# Sheet1.net
KiCad netlist of a schematic drawn in Altium Designer
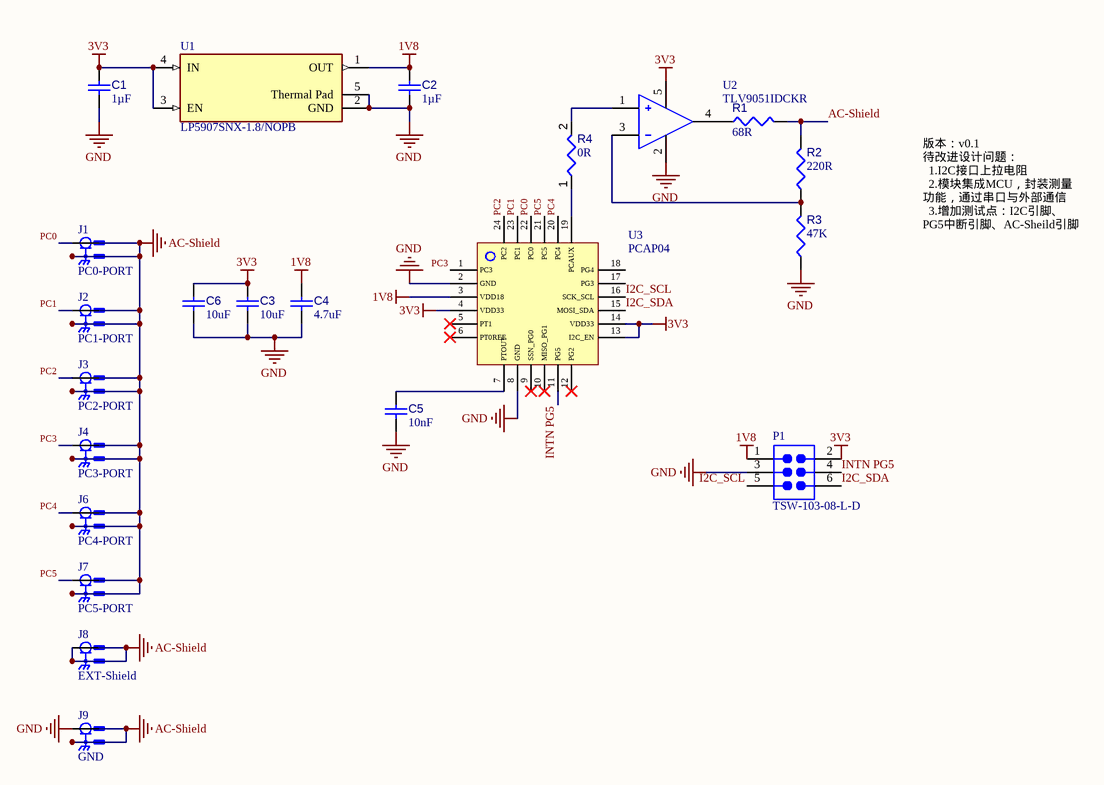
[diagram p0: Sheet1.SchDoc]

(export (version "E")
  (design (tool "Eeschema 10.0.6"))
  (components
    (comp (ref "C1")
      (value "1µF")
      (footprint "CAPC0402(1005)60_L")
      (description "Chip Capacitor, 1µF +/-20%, 10V, 0402, Thickness 0.6 mm")
      (fields (field (name "TOLERANCE") "10%") (field (name "Comment") "Capacitor 1µF +/-20% 10V 0402"))
      (libsource (lib "DigiPCBA Workspace") (part "CAP-NP-2"))
    )
    (comp (ref "C2")
      (value "1µF")
      (footprint "CAPC0402(1005)60_L")
      (description "Chip Capacitor, 1µF +/-20%, 10V, 0402, Thickness 0.6 mm")
      (fields (field (name "TOLERANCE") "10%") (field (name "Comment") "Capacitor 1µF +/-20% 10V 0402"))
      (libsource (lib "DigiPCBA Workspace") (part "CAP-NP-2"))
    )
    (comp (ref "C3")
      (value "10uF")
      (footprint "CAPC0402(1005)60_L")
      (description "Chip Capacitor, 10µF +/-40%, 6.3V, 0402, Thickness 0.6 mm")
      (fields (field (name "TOLERANCE") "10%") (field (name "Comment") "Capacitor 10µF +/-40% 6.3V 0402"))
      (libsource (lib "DigiPCBA Workspace") (part "CAP-NP-2"))
    )
    (comp (ref "C4")
      (value "4.7uF")
      (footprint "CAPC0402(1005)60_L")
      (description "Chip Capacitor, 10µF +/-40%, 6.3V, 0402, Thickness 0.6 mm")
      (fields (field (name "TOLERANCE") "10%") (field (name "Comment") "Capacitor 10µF +/-40% 6.3V 0402"))
      (libsource (lib "DigiPCBA Workspace") (part "CAP-NP-2"))
    )
    (comp (ref "C5")
      (value "10nF")
      (footprint "CAPC0402(1005)60_L")
      (description "Chip Capacitor, 10nF +/-20%, 50V, 0402, Thickness 0.6 mm")
      (fields (field (name "TOLERANCE") "5%") (field (name "Comment") "Capacitor 10nF +/-20% 50V 0402"))
      (libsource (lib "DigiPCBA Workspace") (part "CAP-NP-2"))
    )
    (comp (ref "C6")
      (value "10uF")
      (footprint "CAPC0402(1005)60_L")
      (description "Chip Capacitor, 10µF +/-40%, 6.3V, 0402, Thickness 0.6 mm")
      (fields (field (name "TOLERANCE") "10%") (field (name "Comment") "Capacitor 10µF +/-40% 6.3V 0402"))
      (libsource (lib "DigiPCBA Workspace") (part "CAP-NP-2"))
    )
    (comp (ref "J1")
      (value "PC0-PORT")
      (footprint "LINX_CONMHF4-SMD-G-T")
      (description "IPEX MHF4 Connector Jack, Male Pin 50Ohm Surface Mount Solder")
      (fields (field (name "MP") "CONMHF4-SMD-G-T") (field (name "MF") "Linx Technologies Inc."))
      (libsource (lib "DigiPCBA Workspace") (part "CONMHF4-SMD-G-T"))
    )
    (comp (ref "J2")
      (value "PC1-PORT")
      (footprint "LINX_CONMHF4-SMD-G-T")
      (description "IPEX MHF4 Connector Jack, Male Pin 50Ohm Surface Mount Solder")
      (fields (field (name "MP") "CONMHF4-SMD-G-T") (field (name "MF") "Linx Technologies Inc."))
      (libsource (lib "DigiPCBA Workspace") (part "CONMHF4-SMD-G-T"))
    )
    (comp (ref "J3")
      (value "PC2-PORT")
      (footprint "LINX_CONMHF4-SMD-G-T")
      (description "IPEX MHF4 Connector Jack, Male Pin 50Ohm Surface Mount Solder")
      (fields (field (name "MP") "CONMHF4-SMD-G-T") (field (name "MF") "Linx Technologies Inc."))
      (libsource (lib "DigiPCBA Workspace") (part "CONMHF4-SMD-G-T"))
    )
    (comp (ref "J4")
      (value "PC3-PORT")
      (footprint "LINX_CONMHF4-SMD-G-T")
      (description "IPEX MHF4 Connector Jack, Male Pin 50Ohm Surface Mount Solder")
      (fields (field (name "MP") "CONMHF4-SMD-G-T") (field (name "MF") "Linx Technologies Inc."))
      (libsource (lib "DigiPCBA Workspace") (part "CONMHF4-SMD-G-T"))
    )
    (comp (ref "J6")
      (value "PC4-PORT")
      (footprint "LINX_CONMHF4-SMD-G-T")
      (description "IPEX MHF4 Connector Jack, Male Pin 50Ohm Surface Mount Solder")
      (fields (field (name "MP") "CONMHF4-SMD-G-T") (field (name "MF") "Linx Technologies Inc."))
      (libsource (lib "DigiPCBA Workspace") (part "CONMHF4-SMD-G-T"))
    )
    (comp (ref "J7")
      (value "PC5-PORT")
      (footprint "LINX_CONMHF4-SMD-G-T")
      (description "IPEX MHF4 Connector Jack, Male Pin 50Ohm Surface Mount Solder")
      (fields (field (name "MP") "CONMHF4-SMD-G-T") (field (name "MF") "Linx Technologies Inc."))
      (libsource (lib "DigiPCBA Workspace") (part "CONMHF4-SMD-G-T"))
    )
    (comp (ref "J8")
      (value "EXT-Shield")
      (footprint "LINX_CONMHF4-SMD-G-T")
      (description "IPEX MHF4 Connector Jack, Male Pin 50Ohm Surface Mount Solder")
      (fields (field (name "MP") "CONMHF4-SMD-G-T") (field (name "MF") "Linx Technologies Inc."))
      (libsource (lib "DigiPCBA Workspace") (part "CONMHF4-SMD-G-T"))
    )
    (comp (ref "J9")
      (value "GND")
      (footprint "LINX_CONMHF4-SMD-G-T")
      (description "IPEX MHF4 Connector Jack, Male Pin 50Ohm Surface Mount Solder")
      (fields (field (name "MP") "CONMHF4-SMD-G-T") (field (name "MF") "Linx Technologies Inc."))
      (libsource (lib "DigiPCBA Workspace") (part "CONMHF4-SMD-G-T"))
    )
    (comp (ref "P1")
      (value "TSW-103-08-L-D")
      (footprint "SMTC-TSW-103-08-X-D")
      (description "0.025\" SQ Post Header, Through-hole, Vertical, -55 to 125 degC, 2.54 mm Pitch, 6-Pin, Male, RoHS")
      (fields (field (name "MANUFACTURER") "Samtec"))
      (libsource (lib "Altium Content Vault") (part "SMTC-TSW-103-08-X-D"))
    )
    (comp (ref "R1")
      (value "68R")
      (footprint "RESC0402(1005)_L")
      (description "Chip Resistor, 10 Ohms, +/-1 %, 63 mW, -55 to 155 degC, 0402")
      (fields (field (name "TOLERANCE") "1%") (field (name "POWER") "63mW"))
      (libsource (lib "DigiPCBA Workspace") (part "RES-2"))
    )
    (comp (ref "R2")
      (value "220R")
      (footprint "RESC0402(1005)_L")
      (description "Chip Resistor, 10 Ohms, +/-1 %, 63 mW, -55 to 155 degC, 0402")
      (fields (field (name "TOLERANCE") "1%") (field (name "POWER") "63mW"))
      (libsource (lib "DigiPCBA Workspace") (part "RES-2"))
    )
    (comp (ref "R3")
      (value "47K")
      (footprint "RESC0402(1005)_L")
      (description "Chip Resistor, 10 Ohms, +/-1 %, 63 mW, -55 to 155 degC, 0402")
      (fields (field (name "TOLERANCE") "1%") (field (name "POWER") "63mW"))
      (libsource (lib "DigiPCBA Workspace") (part "RES-2"))
    )
    (comp (ref "R4")
      (value "0R")
      (footprint "RESC0402(1005)_L")
      (description "Chip Resistor, 10 Ohms, +/-1 %, 63 mW, -55 to 155 degC, 0402")
      (fields (field (name "TOLERANCE") "1%") (field (name "POWER") "63mW"))
      (libsource (lib "") (part "RES-2_1"))
    )
    (comp (ref "U1")
      (value "LP5907SNX-1.8/NOPB")
      (footprint "FP-DQN0004A-MFG")
      (description "None")
      (libsource (lib "Altium Content Vault") (part "d9ea95ee919af165dc366e5aa64fdc0"))
    )
    (comp (ref "U2")
      (value "TLV9051IDCKR")
      (footprint "FP-DCK0005A-IPC_A")
      (description "IC OPAMP GP 1 CIRCUIT SC70-5")
      (libsource (lib "Altium Content Vault") (part "d26da39eff9d56ed2cb7351b5ff93ab"))
    )
    (comp (ref "U3")
      (value "PCAP04")
      (footprint "QFN-24-PAD")
      (description "CDC IC")
      (libsource (lib "Schlib1") (part "PCAP04"))
    )
  )
  (nets
    (net (code "1") (name "/I2C_SCL") (class "Default")
      (node (ref "P1") (pin "5") (pinfunction "5_5") (pintype "passive"))
      (node (ref "U3") (pin "16") (pinfunction "SCK_SCL_16") (pintype "passive"))
    )
    (net (code "2") (name "/I2C_SDA") (class "Default")
      (node (ref "P1") (pin "6") (pinfunction "6_6") (pintype "passive"))
      (node (ref "U3") (pin "15") (pinfunction "MOSI_SDA_15") (pintype "passive"))
    )
    (net (code "3") (name "/INTN PG5") (class "Default")
      (node (ref "P1") (pin "4") (pinfunction "4_4") (pintype "passive"))
      (node (ref "U3") (pin "11") (pinfunction "PG5_11") (pintype "passive"))
    )
    (net (code "4") (name "/PC0") (class "Default")
      (node (ref "J1") (pin "1") (pinfunction "1_1") (pintype "passive"))
      (node (ref "U3") (pin "22") (pinfunction "PC0_22") (pintype "passive"))
    )
    (net (code "5") (name "/PC1") (class "Default")
      (node (ref "J2") (pin "1") (pinfunction "1_1") (pintype "passive"))
      (node (ref "U3") (pin "23") (pinfunction "PC1_23") (pintype "passive"))
    )
    (net (code "6") (name "/PC2") (class "Default")
      (node (ref "J3") (pin "1") (pinfunction "1_1") (pintype "passive"))
      (node (ref "U3") (pin "24") (pinfunction "PC2_24") (pintype "passive"))
    )
    (net (code "7") (name "/PC3") (class "Default")
      (node (ref "J4") (pin "1") (pinfunction "1_1") (pintype "passive"))
      (node (ref "U3") (pin "1") (pinfunction "PC3_1") (pintype "passive"))
    )
    (net (code "8") (name "/PC4") (class "Default")
      (node (ref "J6") (pin "1") (pinfunction "1_1") (pintype "passive"))
      (node (ref "U3") (pin "20") (pinfunction "PC4_20") (pintype "passive"))
    )
    (net (code "9") (name "/PC5") (class "Default")
      (node (ref "J7") (pin "1") (pinfunction "1_1") (pintype "passive"))
      (node (ref "U3") (pin "21") (pinfunction "PC5_21") (pintype "passive"))
    )
    (net (code "10") (name "1V8") (class "Default")
      (node (ref "C2") (pin "1") (pinfunction "1_1") (pintype "passive"))
      (node (ref "C4") (pin "2") (pinfunction "2_2") (pintype "passive"))
      (node (ref "P1") (pin "1") (pinfunction "1_1") (pintype "passive"))
      (node (ref "U1") (pin "1") (pinfunction "OUT_1") (pintype "output"))
      (node (ref "U3") (pin "3") (pinfunction "VDD18_3") (pintype "passive"))
    )
    (net (code "11") (name "3V3") (class "Default")
      (node (ref "C1") (pin "1") (pinfunction "1_1") (pintype "passive"))
      (node (ref "C3") (pin "2") (pinfunction "2_2") (pintype "passive"))
      (node (ref "C6") (pin "2") (pinfunction "2_2") (pintype "passive"))
      (node (ref "P1") (pin "2") (pinfunction "2_2") (pintype "passive"))
      (node (ref "U1") (pin "3") (pinfunction "EN_3") (pintype "input"))
      (node (ref "U1") (pin "4") (pinfunction "IN_4") (pintype "input"))
      (node (ref "U2") (pin "5") (pinfunction "V+_5") (pintype "power_in"))
      (node (ref "U3") (pin "13") (pinfunction "I2C_EN_13") (pintype "passive"))
      (node (ref "U3") (pin "14") (pinfunction "VDD33_14") (pintype "passive"))
      (node (ref "U3") (pin "4") (pinfunction "VDD33_4") (pintype "passive"))
    )
    (net (code "12") (name "AC-Shield") (class "Default")
      (node (ref "J1") (pin "S1") (pinfunction "2_S1") (pintype "passive"))
      (node (ref "J1") (pin "S2") (pinfunction "2_S2") (pintype "passive"))
      (node (ref "J1") (pin "S3") (pinfunction "2_S3") (pintype "passive"))
      (node (ref "J2") (pin "S1") (pinfunction "2_S1") (pintype "passive"))
      (node (ref "J2") (pin "S2") (pinfunction "2_S2") (pintype "passive"))
      (node (ref "J2") (pin "S3") (pinfunction "2_S3") (pintype "passive"))
      (node (ref "J3") (pin "S1") (pinfunction "2_S1") (pintype "passive"))
      (node (ref "J3") (pin "S2") (pinfunction "2_S2") (pintype "passive"))
      (node (ref "J3") (pin "S3") (pinfunction "2_S3") (pintype "passive"))
      (node (ref "J4") (pin "S1") (pinfunction "2_S1") (pintype "passive"))
      (node (ref "J4") (pin "S2") (pinfunction "2_S2") (pintype "passive"))
      (node (ref "J4") (pin "S3") (pinfunction "2_S3") (pintype "passive"))
      (node (ref "J6") (pin "S1") (pinfunction "2_S1") (pintype "passive"))
      (node (ref "J6") (pin "S2") (pinfunction "2_S2") (pintype "passive"))
      (node (ref "J6") (pin "S3") (pinfunction "2_S3") (pintype "passive"))
      (node (ref "J7") (pin "S1") (pinfunction "2_S1") (pintype "passive"))
      (node (ref "J7") (pin "S2") (pinfunction "2_S2") (pintype "passive"))
      (node (ref "J7") (pin "S3") (pinfunction "2_S3") (pintype "passive"))
      (node (ref "J8") (pin "1") (pinfunction "1_1") (pintype "passive"))
      (node (ref "J8") (pin "S1") (pinfunction "2_S1") (pintype "passive"))
      (node (ref "J8") (pin "S2") (pinfunction "2_S2") (pintype "passive"))
      (node (ref "J8") (pin "S3") (pinfunction "2_S3") (pintype "passive"))
      (node (ref "J9") (pin "S1") (pinfunction "2_S1") (pintype "passive"))
      (node (ref "J9") (pin "S2") (pinfunction "2_S2") (pintype "passive"))
      (node (ref "J9") (pin "S3") (pinfunction "2_S3") (pintype "passive"))
      (node (ref "R1") (pin "2") (pinfunction "2_2") (pintype "passive"))
      (node (ref "R2") (pin "2") (pinfunction "2_2") (pintype "passive"))
    )
    (net (code "13") (name "GND") (class "Default")
      (node (ref "C1") (pin "2") (pinfunction "2_2") (pintype "passive"))
      (node (ref "C2") (pin "2") (pinfunction "2_2") (pintype "passive"))
      (node (ref "C3") (pin "1") (pinfunction "1_1") (pintype "passive"))
      (node (ref "C4") (pin "1") (pinfunction "1_1") (pintype "passive"))
      (node (ref "C5") (pin "1") (pinfunction "1_1") (pintype "passive"))
      (node (ref "C6") (pin "1") (pinfunction "1_1") (pintype "passive"))
      (node (ref "J9") (pin "1") (pinfunction "1_1") (pintype "passive"))
      (node (ref "P1") (pin "3") (pinfunction "3_3") (pintype "passive"))
      (node (ref "R3") (pin "1") (pinfunction "1_1") (pintype "passive"))
      (node (ref "U1") (pin "2") (pinfunction "GND_2") (pintype "power_in"))
      (node (ref "U1") (pin "5") (pinfunction "Thermal_Pad_5") (pintype "power_in"))
      (node (ref "U2") (pin "2") (pinfunction "V-_2") (pintype "power_in"))
      (node (ref "U3") (pin "2") (pinfunction "GND_2") (pintype "passive"))
      (node (ref "U3") (pin "8") (pinfunction "GND_8") (pintype "passive"))
    )
    (net (code "14") (name "Net-(U2-IN+)") (class "Default")
      (node (ref "R4") (pin "2") (pinfunction "2_2") (pintype "passive"))
      (node (ref "U2") (pin "1") (pinfunction "IN+_1") (pintype "tri_state"))
    )
    (net (code "15") (name "Net-(U2-IN-)") (class "Default")
      (node (ref "R2") (pin "1") (pinfunction "1_1") (pintype "passive"))
      (node (ref "R3") (pin "2") (pinfunction "2_2") (pintype "passive"))
      (node (ref "U2") (pin "3") (pinfunction "IN-_3") (pintype "tri_state"))
    )
    (net (code "16") (name "Net-(U2-OUT)") (class "Default")
      (node (ref "R1") (pin "1") (pinfunction "1_1") (pintype "passive"))
      (node (ref "U2") (pin "4") (pinfunction "OUT_4") (pintype "passive"))
    )
    (net (code "17") (name "Net-(U3-PCAUX)") (class "Default")
      (node (ref "R4") (pin "1") (pinfunction "1_1") (pintype "passive"))
      (node (ref "U3") (pin "19") (pinfunction "PCAUX_19") (pintype "passive"))
    )
    (net (code "18") (name "Net-(U3-PTOUT)") (class "Default")
      (node (ref "C5") (pin "2") (pinfunction "2_2") (pintype "passive"))
      (node (ref "U3") (pin "7") (pinfunction "PTOUT_7") (pintype "passive"))
    )
    (net (code "19") (name "unconnected-(U3-MISO_PG1-Pad10)") (class "Default")
      (node (ref "U3") (pin "10") (pinfunction "MISO_PG1_10") (pintype "passive+no_connect"))
    )
    (net (code "20") (name "unconnected-(U3-PG2-Pad12)") (class "Default")
      (node (ref "U3") (pin "12") (pinfunction "PG2_12") (pintype "passive+no_connect"))
    )
    (net (code "21") (name "unconnected-(U3-PG3-Pad17)") (class "Default")
      (node (ref "U3") (pin "17") (pinfunction "PG3_17") (pintype "passive"))
    )
    (net (code "22") (name "unconnected-(U3-PG4-Pad18)") (class "Default")
      (node (ref "U3") (pin "18") (pinfunction "PG4_18") (pintype "passive"))
    )
    (net (code "23") (name "unconnected-(U3-PT0REF-Pad6)") (class "Default")
      (node (ref "U3") (pin "6") (pinfunction "PT0REF_6") (pintype "passive+no_connect"))
    )
    (net (code "24") (name "unconnected-(U3-PT1-Pad5)") (class "Default")
      (node (ref "U3") (pin "5") (pinfunction "PT1_5") (pintype "passive+no_connect"))
    )
    (net (code "25") (name "unconnected-(U3-SSN_PG0-Pad9)") (class "Default")
      (node (ref "U3") (pin "9") (pinfunction "SSN_PG0_9") (pintype "passive+no_connect"))
    )
  )
)
